# VestibularVR_H2-module_v1_1.net
KiCad netlist of a schematic drawn in EAGLE
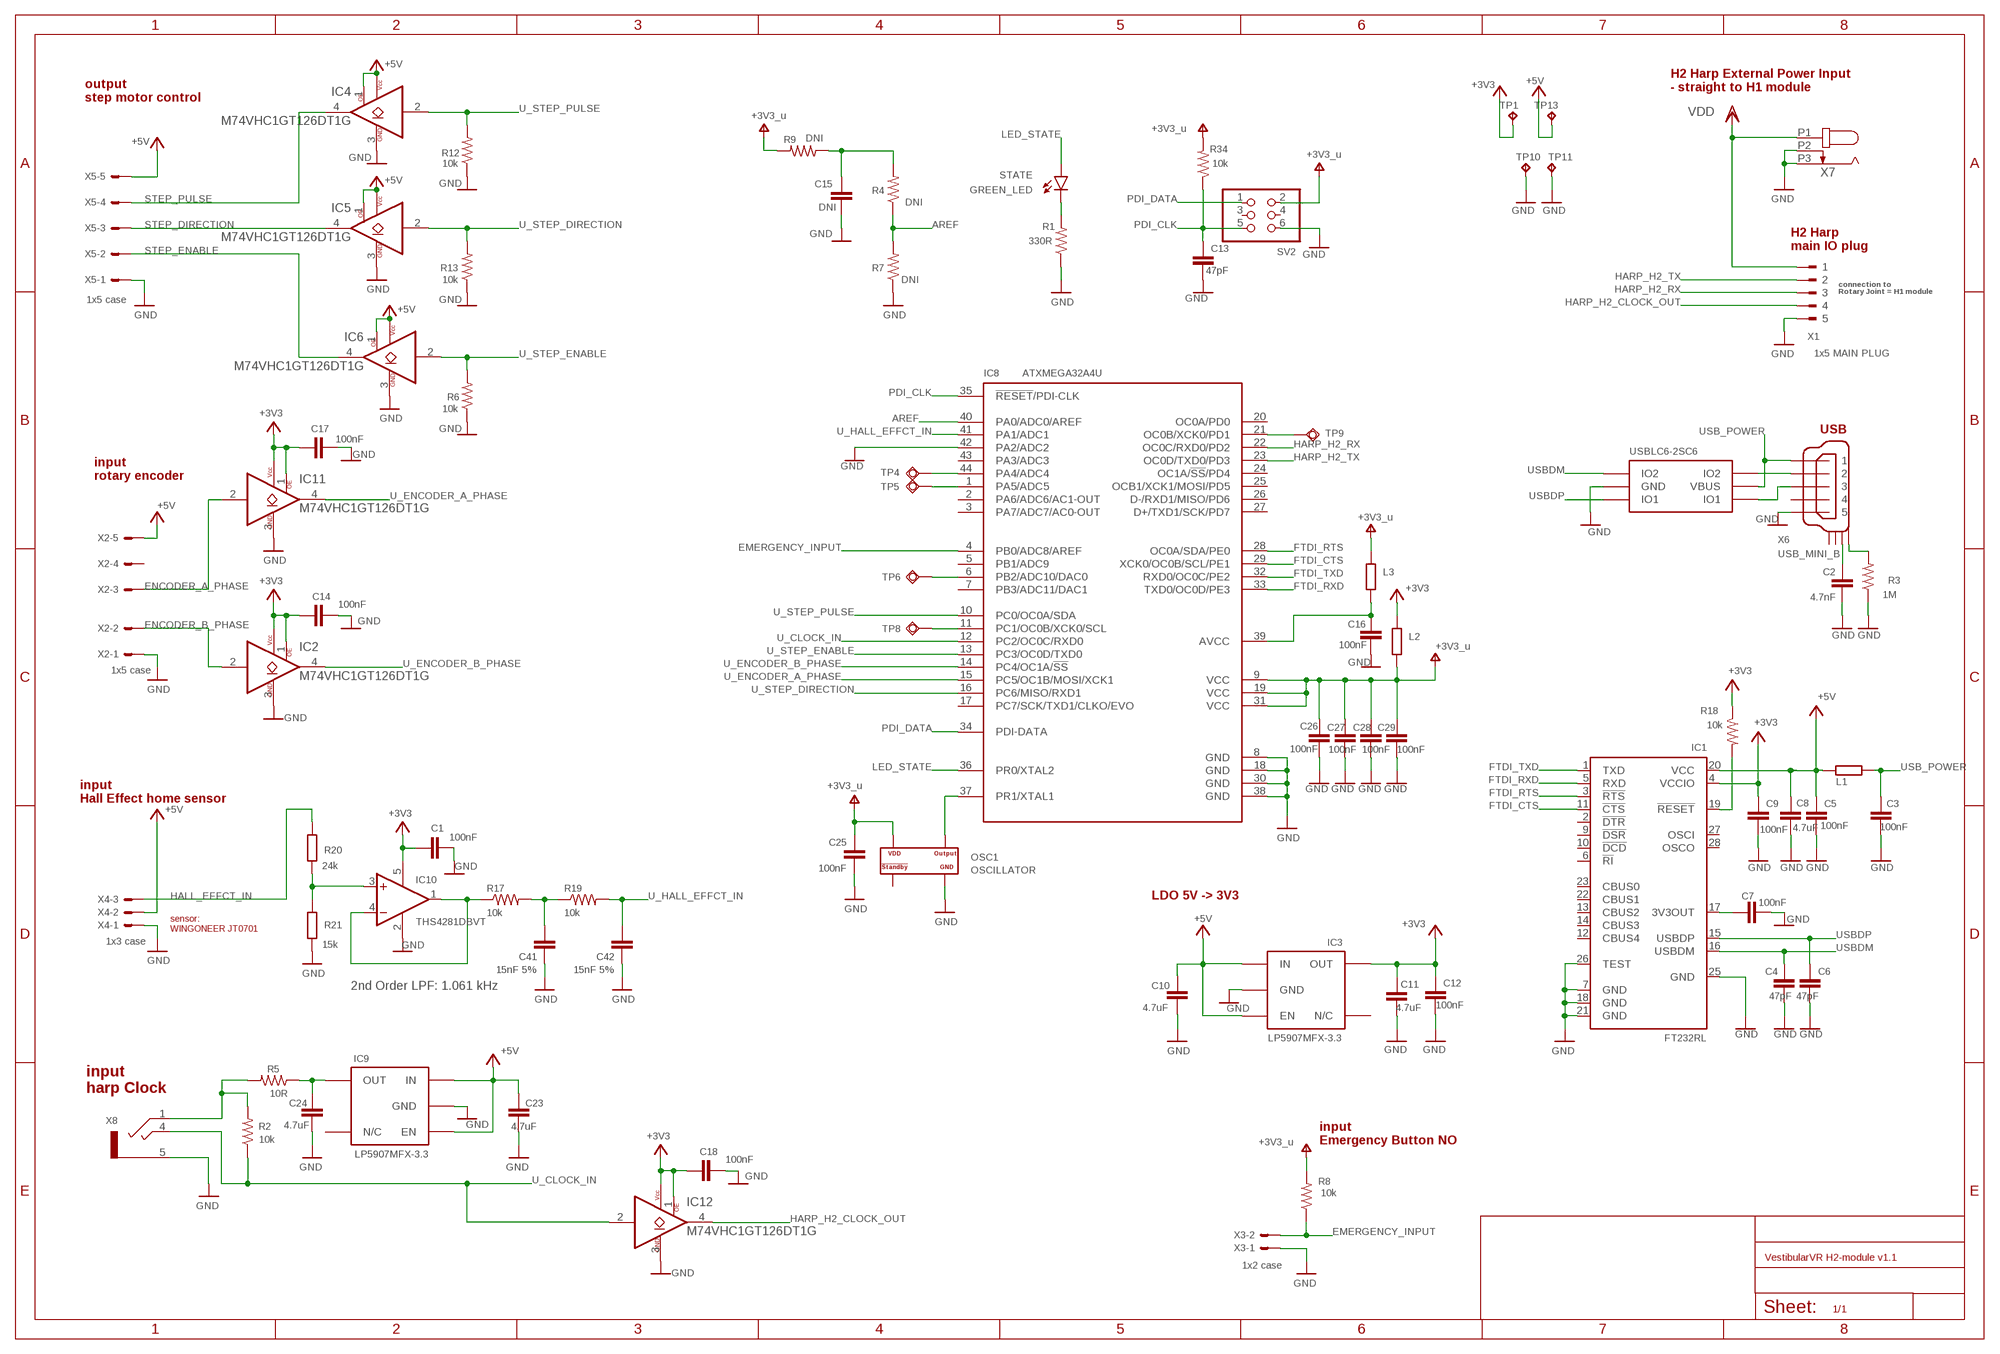
[diagram p0: schematic, sheet 1]

(export (version "E")
  (design (tool "Eeschema 10.0.6"))
  (components
    (comp (ref "C1")
      (value "100nF")
      (footprint "eagle-import:C0402K")
      (fields (field (name "MPN") "C1005X7R1H104K050BB"))
      (libsource (lib "eagle-import") (part "C-EUC0402K"))
    )
    (comp (ref "C2")
      (value "4.7nF")
      (footprint "eagle-import:C0402K")
      (fields (field (name "MPN") "CC0402KRX7R8BB472"))
      (libsource (lib "eagle-import") (part "C-EUC0402K"))
    )
    (comp (ref "C3")
      (value "100nF")
      (footprint "eagle-import:C0402K")
      (fields (field (name "MPN") "C1005X7R1H104K050BB"))
      (libsource (lib "eagle-import") (part "C-EUC0402K"))
    )
    (comp (ref "C4")
      (value "47pF")
      (footprint "eagle-import:C0402K")
      (fields (field (name "MPN") "04025A470JAT2A"))
      (libsource (lib "eagle-import") (part "C-EUC0402K"))
    )
    (comp (ref "C5")
      (value "100nF")
      (footprint "eagle-import:C0402K")
      (fields (field (name "MPN") "C1005X7R1H104K050BB"))
      (libsource (lib "eagle-import") (part "C-EUC0402K"))
    )
    (comp (ref "C6")
      (value "47pF")
      (footprint "eagle-import:C0402K")
      (fields (field (name "MPN") "04025A470JAT2A"))
      (libsource (lib "eagle-import") (part "C-EUC0402K"))
    )
    (comp (ref "C7")
      (value "100nF")
      (footprint "eagle-import:C0402K")
      (fields (field (name "MPN") "C1005X7R1H104K050BB"))
      (libsource (lib "eagle-import") (part "C-EUC0402K"))
    )
    (comp (ref "C8")
      (value "4.7uF")
      (footprint "eagle-import:C0603K")
      (fields (field (name "MPN") "C1608X6S1C475K080AC"))
      (libsource (lib "eagle-import") (part "C-EUC0603K"))
    )
    (comp (ref "C9")
      (value "100nF")
      (footprint "eagle-import:C0402K")
      (fields (field (name "MPN") "C1005X7R1H104K050BB"))
      (libsource (lib "eagle-import") (part "C-EUC0402K"))
    )
    (comp (ref "C10")
      (value "4.7uF")
      (footprint "eagle-import:C0603K")
      (fields (field (name "MPN") "C1608X6S1C475K080AC"))
      (libsource (lib "eagle-import") (part "C-EUC0603K"))
    )
    (comp (ref "C11")
      (value "4.7uF")
      (footprint "eagle-import:C0603K")
      (fields (field (name "MPN") "C1608X6S1C475K080AC"))
      (libsource (lib "eagle-import") (part "C-EUC0603K"))
    )
    (comp (ref "C12")
      (value "100nF")
      (footprint "eagle-import:C0402K")
      (fields (field (name "MPN") "C1005X7R1H104K050BB"))
      (libsource (lib "eagle-import") (part "C-EUC0402K"))
    )
    (comp (ref "C13")
      (value "47pF")
      (footprint "eagle-import:C0402K")
      (fields (field (name "MPN") "04025A470JAT2A"))
      (libsource (lib "eagle-import") (part "C-EUC0402K"))
    )
    (comp (ref "C14")
      (value "100nF")
      (footprint "eagle-import:C0402K")
      (fields (field (name "MPN") "C1005X7R1H104K050BB"))
      (libsource (lib "eagle-import") (part "C-EUC0402K"))
    )
    (comp (ref "C15")
      (value "DNI")
      (footprint "eagle-import:C0603K")
      (libsource (lib "eagle-import") (part "C-EUC0603K"))
    )
    (comp (ref "C16")
      (value "100nF")
      (footprint "eagle-import:C0402K")
      (fields (field (name "MPN") "C1005X7R1H104K050BB"))
      (libsource (lib "eagle-import") (part "C-EUC0402K"))
    )
    (comp (ref "C17")
      (value "100nF")
      (footprint "eagle-import:C0402K")
      (fields (field (name "MPN") "C1005X7R1H104K050BB"))
      (libsource (lib "eagle-import") (part "C-EUC0402K"))
    )
    (comp (ref "C18")
      (value "100nF")
      (footprint "eagle-import:C0402K")
      (fields (field (name "MPN") "C1005X7R1H104K050BB"))
      (libsource (lib "eagle-import") (part "C-EUC0402K"))
    )
    (comp (ref "C23")
      (value "4.7uF")
      (footprint "eagle-import:C0603K")
      (fields (field (name "MPN") "C1608X6S1C475K080AC"))
      (libsource (lib "eagle-import") (part "C-EUC0603K"))
    )
    (comp (ref "C24")
      (value "4.7uF")
      (footprint "eagle-import:C0603K")
      (fields (field (name "MPN") "C1608X6S1C475K080AC"))
      (libsource (lib "eagle-import") (part "C-EUC0603K"))
    )
    (comp (ref "C25")
      (value "100nF")
      (footprint "eagle-import:C0402K")
      (fields (field (name "MPN") "C1005X7R1H104K050BB"))
      (libsource (lib "eagle-import") (part "C-EUC0402K"))
    )
    (comp (ref "C26")
      (value "100nF")
      (footprint "eagle-import:C0402K")
      (fields (field (name "MPN") "C1005X7R1H104K050BB"))
      (libsource (lib "eagle-import") (part "C-EUC0402K"))
    )
    (comp (ref "C27")
      (value "100nF")
      (footprint "eagle-import:C0402K")
      (fields (field (name "MPN") "C1005X7R1H104K050BB"))
      (libsource (lib "eagle-import") (part "C-EUC0402K"))
    )
    (comp (ref "C28")
      (value "100nF")
      (footprint "eagle-import:C0402K")
      (fields (field (name "MPN") "C1005X7R1H104K050BB"))
      (libsource (lib "eagle-import") (part "C-EUC0402K"))
    )
    (comp (ref "C29")
      (value "100nF")
      (footprint "eagle-import:C0402K")
      (fields (field (name "MPN") "C1005X7R1H104K050BB"))
      (libsource (lib "eagle-import") (part "C-EUC0402K"))
    )
    (comp (ref "C41")
      (value "15nF 5%")
      (footprint "eagle-import:C0402K")
      (fields (field (name "MPN") "CGA2B3X7R1V153K050BB"))
      (libsource (lib "eagle-import") (part "C-EUC0402K"))
    )
    (comp (ref "C42")
      (value "15nF 5%")
      (footprint "eagle-import:C0402K")
      (fields (field (name "MPN") "CGA2B3X7R1V153K050BB"))
      (libsource (lib "eagle-import") (part "C-EUC0402K"))
    )
    (comp (ref "IC1")
      (value "FT232RL")
      (footprint "eagle-import:SSOP28")
      (libsource (lib "eagle-import") (part "FT232RL"))
    )
    (comp (ref "IC2")
      (value "M74VHC1GT126DT1G")
      (footprint "eagle-import:TSOP-5")
      (libsource (lib "eagle-import") (part "M74VHC1GT126DT1G"))
    )
    (comp (ref "IC3")
      (value "LP5907MFX-3.3")
      (footprint "eagle-import:TSOT23-5")
      (fields (field (name "MPN") "LP5907MFX-3.3/NOPB"))
      (libsource (lib "eagle-import") (part "TLV700XX"))
    )
    (comp (ref "IC4")
      (value "M74VHC1GT126DT1G")
      (footprint "eagle-import:TSOP-5")
      (libsource (lib "eagle-import") (part "M74VHC1GT126DT1G"))
    )
    (comp (ref "IC5")
      (value "M74VHC1GT126DT1G")
      (footprint "eagle-import:TSOP-5")
      (libsource (lib "eagle-import") (part "M74VHC1GT126DT1G"))
    )
    (comp (ref "IC6")
      (value "M74VHC1GT126DT1G")
      (footprint "eagle-import:TSOP-5")
      (libsource (lib "eagle-import") (part "M74VHC1GT126DT1G"))
    )
    (comp (ref "IC7")
      (value "USBLC6-2SC6")
      (footprint "eagle-import:SOT23-6L")
      (libsource (lib "eagle-import") (part "USBLC6-2SC6"))
    )
    (comp (ref "IC8")
      (value "ATXMEGA32A4U")
      (footprint "eagle-import:TQFP44")
      (fields (field (name "MPN") "ATXMEGA32A4U-AUR"))
      (libsource (lib "eagle-import") (part "XMEGA-A4_AT-XMEGA-XXA4-AUTQFP44"))
    )
    (comp (ref "IC9")
      (value "LP5907MFX-3.3")
      (footprint "eagle-import:TSOT23-5")
      (fields (field (name "MPN") "LP5907MFX-3.3/NOPB"))
      (libsource (lib "eagle-import") (part "TLV700XX"))
    )
    (comp (ref "IC10")
      (value "THS4281DBVT")
      (footprint "eagle-import:SOT23-5")
      (libsource (lib "eagle-import") (part "OPA365"))
    )
    (comp (ref "IC11")
      (value "M74VHC1GT126DT1G")
      (footprint "eagle-import:TSOP-5")
      (libsource (lib "eagle-import") (part "M74VHC1GT126DT1G"))
    )
    (comp (ref "IC12")
      (value "M74VHC1GT126DT1G")
      (footprint "eagle-import:TSOP-5")
      (libsource (lib "eagle-import") (part "M74VHC1GT126DT1G"))
    )
    (comp (ref "L1")
      (value "40R@100MHz")
      (footprint "eagle-import:R0805")
      (fields (field (name "MPN") "MI0805K400R-10"))
      (libsource (lib "eagle-import") (part "R-EU_R0805"))
    )
    (comp (ref "L2")
      (value "40R@100MHz")
      (footprint "eagle-import:R0805")
      (fields (field (name "MPN") "MI0805K400R-10"))
      (libsource (lib "eagle-import") (part "R-EU_R0805"))
    )
    (comp (ref "L3")
      (value "40R@100MHz")
      (footprint "eagle-import:R0805")
      (fields (field (name "MPN") "MI0805K400R-10"))
      (libsource (lib "eagle-import") (part "R-EU_R0805"))
    )
    (comp (ref "OSC1")
      (value "OSCILLATOR")
      (footprint "eagle-import:OSCILLATOR_3.2X2.5")
      (fields (field (name "MPN") "DSC1001CI5-032.0000"))
      (libsource (lib "eagle-import") (part "OSCILLATOR"))
    )
    (comp (ref "R1")
      (value "330R")
      (footprint "eagle-import:R0402")
      (fields (field (name "MPN") "RC0402FR-07330RL"))
      (libsource (lib "eagle-import") (part "R-US_R0402"))
    )
    (comp (ref "R2")
      (value "10k")
      (footprint "eagle-import:R0402")
      (fields (field (name "MPN") "CRCW040210K0FKED"))
      (libsource (lib "eagle-import") (part "R-US_R0402"))
    )
    (comp (ref "R3")
      (value "1M")
      (footprint "eagle-import:R0402")
      (fields (field (name "MPN") "CRCW04021M00FKED"))
      (libsource (lib "eagle-import") (part "R-US_R0402"))
    )
    (comp (ref "R4")
      (value "DNI")
      (footprint "eagle-import:R0402")
      (libsource (lib "eagle-import") (part "R-US_R0402"))
    )
    (comp (ref "R5")
      (value "10R")
      (footprint "eagle-import:R0402")
      (fields (field (name "MPN") "ERJ-PA2J100X "))
      (libsource (lib "eagle-import") (part "R-US_R0402"))
    )
    (comp (ref "R6")
      (value "10k")
      (footprint "eagle-import:R0402")
      (fields (field (name "MPN") "CRCW040210K0FKED"))
      (libsource (lib "eagle-import") (part "R-US_R0402"))
    )
    (comp (ref "R7")
      (value "DNI")
      (footprint "eagle-import:R0402")
      (libsource (lib "eagle-import") (part "R-US_R0402"))
    )
    (comp (ref "R8")
      (value "10k")
      (footprint "eagle-import:R0402")
      (fields (field (name "MPN") "CRCW040210K0FKED"))
      (libsource (lib "eagle-import") (part "R-US_R0402"))
    )
    (comp (ref "R9")
      (value "DNI")
      (footprint "eagle-import:R0402")
      (libsource (lib "eagle-import") (part "R-US_R0402"))
    )
    (comp (ref "R12")
      (value "10k")
      (footprint "eagle-import:R0402")
      (fields (field (name "MPN") "CRCW040210K0FKED"))
      (libsource (lib "eagle-import") (part "R-US_R0402"))
    )
    (comp (ref "R13")
      (value "10k")
      (footprint "eagle-import:R0402")
      (fields (field (name "MPN") "CRCW040210K0FKED"))
      (libsource (lib "eagle-import") (part "R-US_R0402"))
    )
    (comp (ref "R17")
      (value "10k")
      (footprint "eagle-import:R0402")
      (fields (field (name "MPN") "CRCW040210K0FKED"))
      (libsource (lib "eagle-import") (part "R-US_R0402"))
    )
    (comp (ref "R18")
      (value "10k")
      (footprint "eagle-import:R0402")
      (fields (field (name "MPN") "CRCW040210K0FKED"))
      (libsource (lib "eagle-import") (part "R-US_R0402"))
    )
    (comp (ref "R19")
      (value "10k")
      (footprint "eagle-import:R0402")
      (fields (field (name "MPN") "CRCW040210K0FKED"))
      (libsource (lib "eagle-import") (part "R-US_R0402"))
    )
    (comp (ref "R20")
      (value "24k")
      (footprint "eagle-import:R0402")
      (fields (field (name "MPN") "ERJ-2RKF2402X"))
      (libsource (lib "eagle-import") (part "R-EU_R0402"))
    )
    (comp (ref "R21")
      (value "15k")
      (footprint "eagle-import:R0402")
      (fields (field (name "MPN") "ERJ-2RKF1502X"))
      (libsource (lib "eagle-import") (part "R-EU_R0402"))
    )
    (comp (ref "R34")
      (value "10k")
      (footprint "eagle-import:R0402")
      (fields (field (name "MPN") "CRCW040210K0FKED"))
      (libsource (lib "eagle-import") (part "R-US_R0402"))
    )
    (comp (ref "STATE")
      (value "GREEN_LED")
      (footprint "eagle-import:CHIP-LED0603")
      (fields (field (name "MPN") "LTST-C191KGKT"))
      (libsource (lib "eagle-import") (part "LEDCHIP-LED0603"))
    )
    (comp (ref "SV2")
      (value "PINHD-2X3")
      (footprint "eagle-import:2X03")
      (fields (field (name "MPN") "609-3210-ND"))
      (libsource (lib "eagle-import") (part "PINHD-2X3"))
    )
    (comp (ref "TP1")
      (value "NO_COMPONENT")
      (footprint "eagle-import:B1,27")
      (libsource (lib "eagle-import") (part "TPB1,27"))
    )
    (comp (ref "TP4")
      (value "NO_COMPONENT")
      (footprint "eagle-import:TP11R")
      (libsource (lib "eagle-import") (part "TPSQTP11R"))
    )
    (comp (ref "TP5")
      (value "NO_COMPONENT")
      (footprint "eagle-import:TP11R")
      (libsource (lib "eagle-import") (part "TPSQTP11R"))
    )
    (comp (ref "TP6")
      (value "NO_COMPONENT")
      (footprint "eagle-import:TP11R")
      (libsource (lib "eagle-import") (part "TPSQTP11R"))
    )
    (comp (ref "TP8")
      (value "NO_COMPONENT")
      (footprint "eagle-import:TP11R")
      (libsource (lib "eagle-import") (part "TPSQTP11R"))
    )
    (comp (ref "TP9")
      (value "NO_COMPONENT")
      (footprint "eagle-import:TP11R")
      (libsource (lib "eagle-import") (part "TPSQTP11R"))
    )
    (comp (ref "TP10")
      (value "NO_COMPONENT")
      (footprint "eagle-import:B1,27")
      (libsource (lib "eagle-import") (part "TPB1,27"))
    )
    (comp (ref "TP11")
      (value "NO_COMPONENT")
      (footprint "eagle-import:B1,27")
      (libsource (lib "eagle-import") (part "TPB1,27"))
    )
    (comp (ref "TP13")
      (value "NO_COMPONENT")
      (footprint "eagle-import:B1,27")
      (libsource (lib "eagle-import") (part "TPB1,27"))
    )
    (comp (ref "X1")
      (value "1x5 MAIN PLUG")
      (footprint "eagle-import:90G-5")
      (fields (field (name "MPN") "20.155MH/5-E"))
      (libsource (lib "eagle-import") (part "90G-5"))
    )
    (comp (ref "X2")
      (value "1x5 case")
      (footprint "eagle-import:22-23-2051")
      (fields (field (name "MPN") "282834-5") (field (name "OEPS") "OEPS070041"))
      (libsource (lib "eagle-import") (part "22-23-2051"))
    )
    (comp (ref "X3")
      (value "1x2 case")
      (footprint "eagle-import:22-23-2021")
      (fields (field (name "MPN") "282834-2"))
      (libsource (lib "eagle-import") (part "22-23-2021"))
    )
    (comp (ref "X4")
      (value "1x3 case")
      (footprint "eagle-import:22-23-2031")
      (fields (field (name "MPN") "282834-3") (field (name "OEPS") "OEPS070035"))
      (libsource (lib "eagle-import") (part "22-23-2031"))
    )
    (comp (ref "X5")
      (value "1x5 case")
      (footprint "eagle-import:22-23-2051")
      (fields (field (name "MPN") "282834-5") (field (name "OEPS") "OEPS070041"))
      (libsource (lib "eagle-import") (part "22-23-2051"))
    )
    (comp (ref "X6")
      (value "USB_MINI_B")
      (footprint "eagle-import:240-0002-1")
      (fields (field (name "MPN") "UX60-MB-5S8"))
      (libsource (lib "eagle-import") (part "USB_MINI_B"))
    )
    (comp (ref "X7")
      (value "DC_JACK2.1MM")
      (footprint "eagle-import:DC_POWER_INPUT_2.1MM")
      (fields (field (name "MPN") "163-179PH-EX"))
      (libsource (lib "eagle-import") (part "DC_JACK2.1MM"))
    )
    (comp (ref "X8")
      (value "CLCK_JACK")
      (footprint "eagle-import:35RASMT2BHNTRX")
      (fields (field (name "MPN") "35RASMT2BHNTRX"))
      (libsource (lib "eagle-import") (part "STEREO_JACK"))
    )
  )
  (nets
    (net (code "1") (name "+3V3") (class "Default")
      (node (ref "C1") (pin "1") (pinfunction "1_1") (pintype "passive"))
      (node (ref "C11") (pin "1") (pinfunction "1_1") (pintype "passive"))
      (node (ref "C12") (pin "1") (pinfunction "1_1") (pintype "passive"))
      (node (ref "C14") (pin "1") (pinfunction "1_1") (pintype "passive"))
      (node (ref "C17") (pin "1") (pinfunction "1_1") (pintype "passive"))
      (node (ref "C18") (pin "1") (pinfunction "1_1") (pintype "passive"))
      (node (ref "C9") (pin "1") (pinfunction "1_1") (pintype "passive"))
      (node (ref "IC1") (pin "4") (pinfunction "VCCIO_4") (pintype "power_in"))
      (node (ref "IC10") (pin "5") (pinfunction "V+_5") (pintype "power_in"))
      (node (ref "IC11") (pin "1") (pinfunction "OE_1") (pintype "bidirectional"))
      (node (ref "IC11") (pin "5") (pinfunction "VCC_5") (pintype "bidirectional"))
      (node (ref "IC12") (pin "1") (pinfunction "OE_1") (pintype "bidirectional"))
      (node (ref "IC12") (pin "5") (pinfunction "VCC_5") (pintype "bidirectional"))
      (node (ref "IC2") (pin "1") (pinfunction "OE_1") (pintype "bidirectional"))
      (node (ref "IC2") (pin "5") (pinfunction "VCC_5") (pintype "bidirectional"))
      (node (ref "IC3") (pin "5") (pinfunction "OUT_5") (pintype "bidirectional"))
      (node (ref "L2") (pin "2") (pinfunction "2_2") (pintype "passive"))
      (node (ref "R18") (pin "1") (pinfunction "1_1") (pintype "passive"))
      (node (ref "TP1") (pin "TP") (pinfunction "TP_TP") (pintype "input"))
    )
    (net (code "2") (name "+3V3_u") (class "Default")
      (node (ref "C25") (pin "1") (pinfunction "1_1") (pintype "passive"))
      (node (ref "C26") (pin "1") (pinfunction "1_1") (pintype "passive"))
      (node (ref "C27") (pin "1") (pinfunction "1_1") (pintype "passive"))
      (node (ref "C28") (pin "1") (pinfunction "1_1") (pintype "passive"))
      (node (ref "C29") (pin "1") (pinfunction "1_1") (pintype "passive"))
      (node (ref "IC8") (pin "19") (pinfunction "VCC_19") (pintype "power_in"))
      (node (ref "IC8") (pin "31") (pinfunction "VCC_31") (pintype "power_in"))
      (node (ref "IC8") (pin "9") (pinfunction "VCC_9") (pintype "power_in"))
      (node (ref "L2") (pin "1") (pinfunction "1_1") (pintype "passive"))
      (node (ref "L3") (pin "2") (pinfunction "2_2") (pintype "passive"))
      (node (ref "OSC1") (pin "P$4") (pinfunction "VDD_P$4") (pintype "passive"))
      (node (ref "R34") (pin "2") (pinfunction "2_2") (pintype "passive"))
      (node (ref "R8") (pin "2") (pinfunction "2_2") (pintype "passive"))
      (node (ref "R9") (pin "2") (pinfunction "2_2") (pintype "passive"))
      (node (ref "SV2") (pin "2") (pinfunction "2_2") (pintype "passive"))
    )
    (net (code "3") (name "+5V") (class "Default")
      (node (ref "C10") (pin "1") (pinfunction "1_1") (pintype "passive"))
      (node (ref "C23") (pin "1") (pinfunction "1_1") (pintype "passive"))
      (node (ref "C5") (pin "1") (pinfunction "1_1") (pintype "passive"))
      (node (ref "C8") (pin "1") (pinfunction "1_1") (pintype "passive"))
      (node (ref "IC1") (pin "20") (pinfunction "VCC_20") (pintype "power_in"))
      (node (ref "IC3") (pin "1") (pinfunction "IN_1") (pintype "bidirectional"))
      (node (ref "IC3") (pin "3") (pinfunction "EN_3") (pintype "bidirectional"))
      (node (ref "IC4") (pin "1") (pinfunction "OE_1") (pintype "bidirectional"))
      (node (ref "IC4") (pin "5") (pinfunction "VCC_5") (pintype "bidirectional"))
      (node (ref "IC5") (pin "1") (pinfunction "OE_1") (pintype "bidirectional"))
      (node (ref "IC5") (pin "5") (pinfunction "VCC_5") (pintype "bidirectional"))
      (node (ref "IC6") (pin "1") (pinfunction "OE_1") (pintype "bidirectional"))
      (node (ref "IC6") (pin "5") (pinfunction "VCC_5") (pintype "bidirectional"))
      (node (ref "IC9") (pin "1") (pinfunction "IN_1") (pintype "bidirectional"))
      (node (ref "IC9") (pin "3") (pinfunction "EN_3") (pintype "bidirectional"))
      (node (ref "L1") (pin "1") (pinfunction "1_1") (pintype "passive"))
      (node (ref "TP13") (pin "TP") (pinfunction "TP_TP") (pintype "input"))
      (node (ref "X2") (pin "5") (pinfunction "S_5") (pintype "passive"))
      (node (ref "X4") (pin "2") (pinfunction "S_2") (pintype "passive"))
      (node (ref "X5") (pin "5") (pinfunction "S_5") (pintype "passive"))
    )
    (net (code "4") (name "/AREF") (class "Default")
      (node (ref "IC8") (pin "40") (pinfunction "PA0/ADC0/AREF_40") (pintype "bidirectional"))
      (node (ref "R4") (pin "1") (pinfunction "1_1") (pintype "passive"))
      (node (ref "R7") (pin "2") (pinfunction "2_2") (pintype "passive"))
    )
    (net (code "5") (name "/EMERGENCY_INPUT") (class "Default")
      (node (ref "IC8") (pin "4") (pinfunction "PB0/ADC8/AREF_4") (pintype "bidirectional"))
      (node (ref "R8") (pin "1") (pinfunction "1_1") (pintype "passive"))
      (node (ref "X3") (pin "2") (pinfunction "S_2") (pintype "passive"))
    )
    (net (code "6") (name "/ENCODER_A_PHASE") (class "Default")
      (node (ref "IC11") (pin "2") (pinfunction "A_2") (pintype "bidirectional"))
      (node (ref "X2") (pin "3") (pinfunction "S_3") (pintype "passive"))
    )
    (net (code "7") (name "/ENCODER_B_PHASE") (class "Default")
      (node (ref "IC2") (pin "2") (pinfunction "A_2") (pintype "bidirectional"))
      (node (ref "X2") (pin "2") (pinfunction "S_2") (pintype "passive"))
    )
    (net (code "8") (name "/FTDI_CTS") (class "Default")
      (node (ref "IC1") (pin "11") (pinfunction "~{CTS}_11") (pintype "input"))
      (node (ref "IC8") (pin "29") (pinfunction "XCK0/OC0B/SCL/PE1_29") (pintype "bidirectional"))
    )
    (net (code "9") (name "/FTDI_RTS") (class "Default")
      (node (ref "IC1") (pin "3") (pinfunction "~{RTS}_3") (pintype "output"))
      (node (ref "IC8") (pin "28") (pinfunction "OC0A/SDA/PE0_28") (pintype "bidirectional"))
    )
    (net (code "10") (name "/FTDI_RXD") (class "Default")
      (node (ref "IC1") (pin "5") (pinfunction "RXD_5") (pintype "input"))
      (node (ref "IC8") (pin "33") (pinfunction "TXD0/OC0D/PE3_33") (pintype "bidirectional"))
    )
    (net (code "11") (name "/FTDI_TXD") (class "Default")
      (node (ref "IC1") (pin "1") (pinfunction "TXD_1") (pintype "output"))
      (node (ref "IC8") (pin "32") (pinfunction "RXD0/OC0C/PE2_32") (pintype "bidirectional"))
    )
    (net (code "12") (name "/HALL_EFFCT_IN") (class "Default")
      (node (ref "R20") (pin "2") (pinfunction "2_2") (pintype "passive"))
      (node (ref "X4") (pin "3") (pinfunction "S_3") (pintype "passive"))
    )
    (net (code "13") (name "/HARP_H2_CLOCK_OUT") (class "Default")
      (node (ref "IC12") (pin "4") (pinfunction "Y_4") (pintype "bidirectional"))
      (node (ref "X1") (pin "4") (pinfunction "4_4") (pintype "passive"))
    )
    (net (code "14") (name "/HARP_H2_RX") (class "Default")
      (node (ref "IC8") (pin "22") (pinfunction "OC0C/RXD0/PD2_22") (pintype "bidirectional"))
      (node (ref "X1") (pin "3") (pinfunction "3_3") (pintype "passive"))
    )
    (net (code "15") (name "/HARP_H2_TX") (class "Default")
      (node (ref "IC8") (pin "23") (pinfunction "OC0D/TXD0/PD3_23") (pintype "bidirectional"))
      (node (ref "X1") (pin "2") (pinfunction "2_2") (pintype "passive"))
    )
    (net (code "16") (name "/LED_STATE") (class "Default")
      (node (ref "IC8") (pin "36") (pinfunction "PR0/XTAL2_36") (pintype "bidirectional"))
      (node (ref "STATE") (pin "A") (pinfunction "A_A") (pintype "passive"))
    )
    (net (code "17") (name "/PDI_CLK") (class "Default")
      (node (ref "C13") (pin "1") (pinfunction "1_1") (pintype "passive"))
      (node (ref "IC8") (pin "35") (pinfunction "~{RESET}/PDI-CLK_35") (pintype "input"))
      (node (ref "R34") (pin "1") (pinfunction "1_1") (pintype "passive"))
      (node (ref "SV2") (pin "5") (pinfunction "5_5") (pintype "passive"))
    )
    (net (code "18") (name "/PDI_DATA") (class "Default")
      (node (ref "IC8") (pin "34") (pinfunction "PDI-DATA_34") (pintype "bidirectional"))
      (node (ref "SV2") (pin "1") (pinfunction "1_1") (pintype "passive"))
    )
    (net (code "19") (name "/STEP_DIRECTION") (class "Default")
      (node (ref "IC5") (pin "4") (pinfunction "Y_4") (pintype "bidirectional"))
      (node (ref "X5") (pin "3") (pinfunction "S_3") (pintype "passive"))
    )
    (net (code "20") (name "/STEP_ENABLE") (class "Default")
      (node (ref "IC6") (pin "4") (pinfunction "Y_4") (pintype "bidirectional"))
      (node (ref "X5") (pin "2") (pinfunction "S_2") (pintype "passive"))
    )
    (net (code "21") (name "/STEP_PULSE") (class "Default")
      (node (ref "IC4") (pin "4") (pinfunction "Y_4") (pintype "bidirectional"))
      (node (ref "X5") (pin "4") (pinfunction "S_4") (pintype "passive"))
    )
    (net (code "22") (name "/USBDM") (class "Default")
      (node (ref "C4") (pin "1") (pinfunction "1_1") (pintype "passive"))
      (node (ref "IC1") (pin "16") (pinfunction "USBDM_16") (pintype "bidirectional"))
      (node (ref "IC7") (pin "P$3") (pinfunction "IO2_P$3") (pintype "bidirectional"))
    )
    (net (code "23") (name "/USBDP") (class "Default")
      (node (ref "C6") (pin "1") (pinfunction "1_1") (pintype "passive"))
      (node (ref "IC1") (pin "15") (pinfunction "USBDP_15") (pintype "bidirectional"))
      (node (ref "IC7") (pin "P$1") (pinfunction "IO1_P$1") (pintype "bidirectional"))
    )
    (net (code "24") (name "/USB_POWER") (class "Default")
      (node (ref "C3") (pin "1") (pinfunction "1_1") (pintype "passive"))
      (node (ref "IC7") (pin "P$5") (pinfunction "VBUS_P$5") (pintype "bidirectional"))
      (node (ref "L1") (pin "2") (pinfunction "2_2") (pintype "passive"))
      (node (ref "X6") (pin "P$1") (pinfunction "1_P$1") (pintype "bidirectional"))
    )
    (net (code "25") (name "/U_CLOCK_IN") (class "Default")
      (node (ref "IC12") (pin "2") (pinfunction "A_2") (pintype "bidirectional"))
      (node (ref "IC8") (pin "12") (pinfunction "PC2/OC0C/RXD0_12") (pintype "bidirectional"))
      (node (ref "R2") (pin "1") (pinfunction "1_1") (pintype "passive"))
      (node (ref "X8") (pin "4") (pinfunction "4_4") (pintype "passive"))
    )
    (net (code "26") (name "/U_ENCODER_A_PHASE") (class "Default")
      (node (ref "IC11") (pin "4") (pinfunction "Y_4") (pintype "bidirectional"))
      (node (ref "IC8") (pin "15") (pinfunction "PC5/OC1B/MOSI/XCK1_15") (pintype "bidirectional"))
    )
    (net (code "27") (name "/U_ENCODER_B_PHASE") (class "Default")
      (node (ref "IC2") (pin "4") (pinfunction "Y_4") (pintype "bidirectional"))
      (node (ref "IC8") (pin "14") (pinfunction "PC4/OC1A/~{SS}_14") (pintype "bidirectional"))
    )
    (net (code "28") (name "/U_HALL_EFFCT_IN") (class "Default")
      (node (ref "C42") (pin "2") (pinfunction "2_2") (pintype "passive"))
      (node (ref "IC8") (pin "41") (pinfunction "PA1/ADC1_41") (pintype "bidirectional"))
      (node (ref "R19") (pin "2") (pinfunction "2_2") (pintype "passive"))
    )
    (net (code "29") (name "/U_STEP_DIRECTION") (class "Default")
      (node (ref "IC5") (pin "2") (pinfunction "A_2") (pintype "bidirectional"))
      (node (ref "IC8") (pin "16") (pinfunction "PC6/MISO/RXD1_16") (pintype "bidirectional"))
      (node (ref "R13") (pin "2") (pinfunction "2_2") (pintype "passive"))
    )
    (net (code "30") (name "/U_STEP_ENABLE") (class "Default")
      (node (ref "IC6") (pin "2") (pinfunction "A_2") (pintype "bidirectional"))
      (node (ref "IC8") (pin "13") (pinfunction "PC3/OC0D/TXD0_13") (pintype "bidirectional"))
      (node (ref "R6") (pin "2") (pinfunction "2_2") (pintype "passive"))
    )
    (net (code "31") (name "/U_STEP_PULSE") (class "Default")
      (node (ref "IC4") (pin "2") (pinfunction "A_2") (pintype "bidirectional"))
      (node (ref "IC8") (pin "10") (pinfunction "PC0/OC0A/SDA_10") (pintype "bidirectional"))
      (node (ref "R12") (pin "2") (pinfunction "2_2") (pintype "passive"))
    )
    (net (code "32") (name "GND") (class "Default")
      (node (ref "C1") (pin "2") (pinfunction "2_2") (pintype "passive"))
      (node (ref "C10") (pin "2") (pinfunction "2_2") (pintype "passive"))
      (node (ref "C11") (pin "2") (pinfunction "2_2") (pintype "passive"))
      (node (ref "C12") (pin "2") (pinfunction "2_2") (pintype "passive"))
      (node (ref "C13") (pin "2") (pinfunction "2_2") (pintype "passive"))
      (node (ref "C14") (pin "2") (pinfunction "2_2") (pintype "passive"))
      (node (ref "C15") (pin "2") (pinfunction "2_2") (pintype "passive"))
      (node (ref "C16") (pin "2") (pinfunction "2_2") (pintype "passive"))
      (node (ref "C17") (pin "2") (pinfunction "2_2") (pintype "passive"))
      (node (ref "C18") (pin "2") (pinfunction "2_2") (pintype "passive"))
      (node (ref "C2") (pin "2") (pinfunction "2_2") (pintype "passive"))
      (node (ref "C23") (pin "2") (pinfunction "2_2") (pintype "passive"))
      (node (ref "C24") (pin "2") (pinfunction "2_2") (pintype "passive"))
      (node (ref "C25") (pin "2") (pinfunction "2_2") (pintype "passive"))
      (node (ref "C26") (pin "2") (pinfunction "2_2") (pintype "passive"))
      (node (ref "C27") (pin "2") (pinfunction "2_2") (pintype "passive"))
      (node (ref "C28") (pin "2") (pinfunction "2_2") (pintype "passive"))
      (node (ref "C29") (pin "2") (pinfunction "2_2") (pintype "passive"))
      (node (ref "C3") (pin "2") (pinfunction "2_2") (pintype "passive"))
      (node (ref "C4") (pin "2") (pinfunction "2_2") (pintype "passive"))
      (node (ref "C41") (pin "1") (pinfunction "1_1") (pintype "passive"))
      (node (ref "C42") (pin "1") (pinfunction "1_1") (pintype "passive"))
      (node (ref "C5") (pin "2") (pinfunction "2_2") (pintype "passive"))
      (node (ref "C6") (pin "2") (pinfunction "2_2") (pintype "passive"))
      (node (ref "C7") (pin "2") (pinfunction "2_2") (pintype "passive"))
      (node (ref "C8") (pin "2") (pinfunction "2_2") (pintype "passive"))
      (node (ref "C9") (pin "2") (pinfunction "2_2") (pintype "passive"))
      (node (ref "IC1") (pin "18") (pinfunction "GND_18") (pintype "power_in"))
      (node (ref "IC1") (pin "21") (pinfunction "GND_21") (pintype "power_in"))
      (node (ref "IC1") (pin "25") (pinfunction "GND_25") (pintype "power_in"))
      (node (ref "IC1") (pin "26") (pinfunction "TEST_26") (pintype "input"))
      (node (ref "IC1") (pin "7") (pinfunction "GND_7") (pintype "power_in"))
      (node (ref "IC10") (pin "2") (pinfunction "V-_2") (pintype "power_in"))
      (node (ref "IC11") (pin "3") (pinfunction "GND_3") (pintype "bidirectional"))
      (node (ref "IC12") (pin "3") (pinfunction "GND_3") (pintype "bidirectional"))
      (node (ref "IC2") (pin "3") (pinfunction "GND_3") (pintype "bidirectional"))
      (node (ref "IC3") (pin "2") (pinfunction "GND_2") (pintype "bidirectional"))
      (node (ref "IC4") (pin "3") (pinfunction "GND_3") (pintype "bidirectional"))
      (node (ref "IC5") (pin "3") (pinfunction "GND_3") (pintype "bidirectional"))
      (node (ref "IC6") (pin "3") (pinfunction "GND_3") (pintype "bidirectional"))
      (node (ref "IC7") (pin "P$2") (pinfunction "GND_P$2") (pintype "bidirectional"))
      (node (ref "IC8") (pin "18") (pinfunction "GND_18") (pintype "power_in"))
      (node (ref "IC8") (pin "30") (pinfunction "GND_30") (pintype "power_in"))
      (node (ref "IC8") (pin "38") (pinfunction "GND_38") (pintype "power_in"))
      (node (ref "IC8") (pin "42") (pinfunction "PA2/ADC2_42") (pintype "bidirectional"))
      (node (ref "IC8") (pin "8") (pinfunction "GND_8") (pintype "power_in"))
      (node (ref "IC9") (pin "2") (pinfunction "GND_2") (pintype "bidirectional"))
      (node (ref "OSC1") (pin "P$2") (pinfunction "GND_P$2") (pintype "passive"))
      (node (ref "R1") (pin "1") (pinfunction "1_1") (pintype "passive"))
      (node (ref "R12") (pin "1") (pinfunction "1_1") (pintype "passive"))
      (node (ref "R13") (pin "1") (pinfunction "1_1") (pintype "passive"))
      (node (ref "R21") (pin "1") (pinfunction "1_1") (pintype "passive"))
      (node (ref "R3") (pin "1") (pinfunction "1_1") (pintype "passive"))
      (node (ref "R6") (pin "1") (pinfunction "1_1") (pintype "passive"))
      (node (ref "R7") (pin "1") (pinfunction "1_1") (pintype "passive"))
      (node (ref "SV2") (pin "6") (pinfunction "6_6") (pintype "passive"))
      (node (ref "TP10") (pin "TP") (pinfunction "TP_TP") (pintype "input"))
      (node (ref "TP11") (pin "TP") (pinfunction "TP_TP") (pintype "input"))
      (node (ref "X1") (pin "5") (pinfunction "5_5") (pintype "passive"))
      (node (ref "X2") (pin "1") (pinfunction "S_1") (pintype "passive"))
      (node (ref "X3") (pin "1") (pinfunction "S_1") (pintype "passive"))
      (node (ref "X4") (pin "1") (pinfunction "S_1") (pintype "passive"))
      (node (ref "X5") (pin "1") (pinfunction "S_1") (pintype "passive"))
      (node (ref "X6") (pin "P$5") (pinfunction "5_P$5") (pintype "bidirectional"))
      (node (ref "X7") (pin "P2") (pinfunction "2_P2") (pintype "passive"))
      (node (ref "X7") (pin "P3") (pinfunction "3_P3") (pintype "passive"))
      (node (ref "X8") (pin "5") (pinfunction "5_5") (pintype "passive"))
    )
    (net (code "33") (name "Net-(C15-Pad1)") (class "Default")
      (node (ref "C15") (pin "1") (pinfunction "1_1") (pintype "passive"))
      (node (ref "R4") (pin "2") (pinfunction "2_2") (pintype "passive"))
      (node (ref "R9") (pin "1") (pinfunction "1_1") (pintype "passive"))
    )
    (net (code "34") (name "Net-(C41-Pad2)") (class "Default")
      (node (ref "C41") (pin "2") (pinfunction "2_2") (pintype "passive"))
      (node (ref "R17") (pin "2") (pinfunction "2_2") (pintype "passive"))
      (node (ref "R19") (pin "1") (pinfunction "1_1") (pintype "passive"))
    )
    (net (code "35") (name "Net-(IC1-3V3OUT)") (class "Default")
      (node (ref "C7") (pin "1") (pinfunction "1_1") (pintype "passive"))
      (node (ref "IC1") (pin "17") (pinfunction "3V3OUT_17") (pintype "output"))
    )
    (net (code "36") (name "Net-(IC1-~{RESET})") (class "Default")
      (node (ref "IC1") (pin "19") (pinfunction "~{RESET}_19") (pintype "input"))
      (node (ref "R18") (pin "2") (pinfunction "2_2") (pintype "passive"))
    )
    (net (code "37") (name "Net-(IC8-AVCC)") (class "Default")
      (node (ref "C16") (pin "1") (pinfunction "1_1") (pintype "passive"))
      (node (ref "IC8") (pin "39") (pinfunction "AVCC_39") (pintype "power_in"))
      (node (ref "L3") (pin "1") (pinfunction "1_1") (pintype "passive"))
    )
    (net (code "38") (name "Net-(IC8-OC0B{slash}XCK0{slash}PD1)") (class "Default")
      (node (ref "IC8") (pin "21") (pinfunction "OC0B/XCK0/PD1_21") (pintype "bidirectional"))
      (node (ref "TP9") (pin "TP") (pinfunction "TP_TP") (pintype "input"))
    )
    (net (code "39") (name "Net-(IC8-PA4{slash}ADC4)") (class "Default")
      (node (ref "IC8") (pin "44") (pinfunction "PA4/ADC4_44") (pintype "bidirectional"))
      (node (ref "TP4") (pin "TP") (pinfunction "TP_TP") (pintype "input"))
    )
    (net (code "40") (name "Net-(IC8-PA5{slash}ADC5)") (class "Default")
      (node (ref "IC8") (pin "1") (pinfunction "PA5/ADC5_1") (pintype "bidirectional"))
      (node (ref "TP5") (pin "TP") (pinfunction "TP_TP") (pintype "input"))
    )
    (net (code "41") (name "Net-(IC8-PB2{slash}ADC10{slash}DAC0)") (class "Default")
      (node (ref "IC8") (pin "6") (pinfunction "PB2/ADC10/DAC0_6") (pintype "bidirectional"))
      (node (ref "TP6") (pin "TP") (pinfunction "TP_TP") (pintype "input"))
    )
    (net (code "42") (name "Net-(IC8-PC1{slash}OC0B{slash}XCK0{slash}SCL)") (class "Default")
      (node (ref "IC8") (pin "11") (pinfunction "PC1/OC0B/XCK0/SCL_11") (pintype "bidirectional"))
      (node (ref "TP8") (pin "TP") (pinfunction "TP_TP") (pintype "input"))
    )
    (net (code "43") (name "Net-(IC8-PR1{slash}XTAL1)") (class "Default")
      (node (ref "IC8") (pin "37") (pinfunction "PR1/XTAL1_37") (pintype "bidirectional"))
      (node (ref "OSC1") (pin "P$3") (pinfunction "OUTPUT_P$3") (pintype "passive"))
    )
    (net (code "44") (name "Net-(IC9-OUT)") (class "Default")
      (node (ref "C24") (pin "1") (pinfunction "1_1") (pintype "passive"))
      (node (ref "IC9") (pin "5") (pinfunction "OUT_5") (pintype "bidirectional"))
      (node (ref "R5") (pin "1") (pinfunction "1_1") (pintype "passive"))
    )
    (net (code "45") (name "Net-(IC10-+IN)") (class "Default")
      (node (ref "IC10") (pin "3") (pinfunction "+IN_3") (pintype "input"))
      (node (ref "R20") (pin "1") (pinfunction "1_1") (pintype "passive"))
      (node (ref "R21") (pin "2") (pinfunction "2_2") (pintype "passive"))
    )
    (net (code "46") (name "Net-(IC10--IN)") (class "Default")
      (node (ref "IC10") (pin "1") (pinfunction "OUT_1") (pintype "output"))
      (node (ref "IC10") (pin "4") (pinfunction "-IN_4") (pintype "input"))
      (node (ref "R17") (pin "1") (pinfunction "1_1") (pintype "passive"))
    )
    (net (code "47") (name "Net-(R1-Pad2)") (class "Default")
      (node (ref "R1") (pin "2") (pinfunction "2_2") (pintype "passive"))
      (node (ref "STATE") (pin "C") (pinfunction "C_C") (pintype "passive"))
    )
    (net (code "48") (name "Net-(R2-Pad2)") (class "Default")
      (node (ref "R2") (pin "2") (pinfunction "2_2") (pintype "passive"))
      (node (ref "R5") (pin "2") (pinfunction "2_2") (pintype "passive"))
      (node (ref "X8") (pin "1") (pinfunction "1_1") (pintype "passive"))
    )
    (net (code "49") (name "Net-(X6-2)") (class "Default")
      (node (ref "IC7") (pin "P$4") (pinfunction "IO2_P$4") (pintype "bidirectional"))
      (node (ref "X6") (pin "P$2") (pinfunction "2_P$2") (pintype "bidirectional"))
    )
    (net (code "50") (name "Net-(X6-3)") (class "Default")
      (node (ref "IC7") (pin "P$6") (pinfunction "IO1_P$6") (pintype "bidirectional"))
      (node (ref "X6") (pin "P$3") (pinfunction "3_P$3") (pintype "bidirectional"))
    )
    (net (code "51") (name "Net-(X6-P$3)") (class "Default")
      (node (ref "C2") (pin "1") (pinfunction "1_1") (pintype "passive"))
      (node (ref "X6") (pin "SHIELD_3") (pinfunction "P$3_SHIELD_3") (pintype "bidirectional"))
    )
    (net (code "52") (name "Net-(X6-P$4)") (class "Default")
      (node (ref "R3") (pin "2") (pinfunction "2_2") (pintype "passive"))
      (node (ref "X6") (pin "SHIELD_4") (pinfunction "P$4_SHIELD_4") (pintype "bidirectional"))
    )
    (net (code "53") (name "VDD") (class "Default")
      (node (ref "X1") (pin "1") (pinfunction "1_1") (pintype "passive"))
      (node (ref "X7") (pin "P1") (pinfunction "1_P1") (pintype "passive"))
    )
    (net (code "54") (name "unconnected-(IC1-CBUS0-Pad23)") (class "Default")
      (node (ref "IC1") (pin "23") (pinfunction "CBUS0_23") (pintype "bidirectional"))
    )
    (net (code "55") (name "unconnected-(IC1-CBUS1-Pad22)") (class "Default")
      (node (ref "IC1") (pin "22") (pinfunction "CBUS1_22") (pintype "bidirectional"))
    )
    (net (code "56") (name "unconnected-(IC1-CBUS2-Pad13)") (class "Default")
      (node (ref "IC1") (pin "13") (pinfunction "CBUS2_13") (pintype "bidirectional"))
    )
    (net (code "57") (name "unconnected-(IC1-CBUS3-Pad14)") (class "Default")
      (node (ref "IC1") (pin "14") (pinfunction "CBUS3_14") (pintype "bidirectional"))
    )
    (net (code "58") (name "unconnected-(IC1-CBUS4-Pad12)") (class "Default")
      (node (ref "IC1") (pin "12") (pinfunction "CBUS4_12") (pintype "bidirectional"))
    )
    (net (code "59") (name "unconnected-(IC1-OSCI-Pad27)") (class "Default")
      (node (ref "IC1") (pin "27") (pinfunction "OSCI_27") (pintype "input"))
    )
    (net (code "60") (name "unconnected-(IC1-OSCO-Pad28)") (class "Default")
      (node (ref "IC1") (pin "28") (pinfunction "OSCO_28") (pintype "output"))
    )
    (net (code "61") (name "unconnected-(IC1-~{DCD}-Pad10)") (class "Default")
      (node (ref "IC1") (pin "10") (pinfunction "~{DCD}_10") (pintype "input"))
    )
    (net (code "62") (name "unconnected-(IC1-~{DSR}-Pad9)") (class "Default")
      (node (ref "IC1") (pin "9") (pinfunction "~{DSR}_9") (pintype "input"))
    )
    (net (code "63") (name "unconnected-(IC1-~{DTR}-Pad2)") (class "Default")
      (node (ref "IC1") (pin "2") (pinfunction "~{DTR}_2") (pintype "output"))
    )
    (net (code "64") (name "unconnected-(IC1-~{RI}-Pad6)") (class "Default")
      (node (ref "IC1") (pin "6") (pinfunction "~{RI}_6") (pintype "input"))
    )
    (net (code "65") (name "unconnected-(IC3-N{slash}C-Pad4)") (class "Default")
      (node (ref "IC3") (pin "4") (pinfunction "N/C_4") (pintype "bidirectional"))
    )
    (net (code "66") (name "unconnected-(IC8-D+{slash}TXD1{slash}SCK{slash}PD7-Pad27)") (class "Default")
      (node (ref "IC8") (pin "27") (pinfunction "D+/TXD1/SCK/PD7_27") (pintype "bidirectional"))
    )
    (net (code "67") (name "unconnected-(IC8-D-{slash}RXD1{slash}MISO{slash}PD6-Pad26)") (class "Default")
      (node (ref "IC8") (pin "26") (pinfunction "D-/RXD1/MISO/PD6_26") (pintype "bidirectional"))
    )
    (net (code "68") (name "unconnected-(IC8-OC0A{slash}PD0-Pad20)") (class "Default")
      (node (ref "IC8") (pin "20") (pinfunction "OC0A/PD0_20") (pintype "bidirectional"))
    )
    (net (code "69") (name "unconnected-(IC8-OC1A{slash}~{SS}{slash}PD4-Pad24)") (class "Default")
      (node (ref "IC8") (pin "24") (pinfunction "OC1A/~{SS}/PD4_24") (pintype "bidirectional"))
    )
    (net (code "70") (name "unconnected-(IC8-OCB1{slash}XCK1{slash}MOSI{slash}PD5-Pad25)") (class "Default")
      (node (ref "IC8") (pin "25") (pinfunction "OCB1/XCK1/MOSI/PD5_25") (pintype "bidirectional"))
    )
    (net (code "71") (name "unconnected-(IC8-PA3{slash}ADC3-Pad43)") (class "Default")
      (node (ref "IC8") (pin "43") (pinfunction "PA3/ADC3_43") (pintype "bidirectional"))
    )
    (net (code "72") (name "unconnected-(IC8-PA6{slash}ADC6{slash}AC1-OUT-Pad2)") (class "Default")
      (node (ref "IC8") (pin "2") (pinfunction "PA6/ADC6/AC1-OUT_2") (pintype "bidirectional"))
    )
    (net (code "73") (name "unconnected-(IC8-PA7{slash}ADC7{slash}AC0-OUT-Pad3)") (class "Default")
      (node (ref "IC8") (pin "3") (pinfunction "PA7/ADC7/AC0-OUT_3") (pintype "bidirectional"))
    )
    (net (code "74") (name "unconnected-(IC8-PB1{slash}ADC9-Pad5)") (class "Default")
      (node (ref "IC8") (pin "5") (pinfunction "PB1/ADC9_5") (pintype "bidirectional"))
    )
    (net (code "75") (name "unconnected-(IC8-PB3{slash}ADC11{slash}DAC1-Pad7)") (class "Default")
      (node (ref "IC8") (pin "7") (pinfunction "PB3/ADC11/DAC1_7") (pintype "bidirectional"))
    )
    (net (code "76") (name "unconnected-(IC8-PC7{slash}SCK{slash}TXD1{slash}CLKO{slash}EVO-Pad17)") (class "Default")
      (node (ref "IC8") (pin "17") (pinfunction "PC7/SCK/TXD1/CLKO/EVO_17") (pintype "bidirectional"))
    )
    (net (code "77") (name "unconnected-(IC9-N{slash}C-Pad4)") (class "Default")
      (node (ref "IC9") (pin "4") (pinfunction "N/C_4") (pintype "bidirectional"))
    )
    (net (code "78") (name "unconnected-(OSC1-STANDBY#-PadP$1)") (class "Default")
      (node (ref "OSC1") (pin "P$1") (pinfunction "STANDBY#_P$1") (pintype "passive"))
    )
    (net (code "79") (name "unconnected-(SV2-Pad3)") (class "Default")
      (node (ref "SV2") (pin "3") (pinfunction "3_3") (pintype "passive"))
    )
    (net (code "80") (name "unconnected-(SV2-Pad4)") (class "Default")
      (node (ref "SV2") (pin "4") (pinfunction "4_4") (pintype "passive"))
    )
    (net (code "81") (name "unconnected-(X2D-S-Pad4)") (class "Default")
      (node (ref "X2") (pin "4") (pinfunction "S_4") (pintype "passive"))
    )
    (net (code "82") (name "unconnected-(X6-4-PadP$4)") (class "Default")
      (node (ref "X6") (pin "P$4") (pinfunction "4_P$4") (pintype "bidirectional"))
    )
    (net (code "83") (name "unconnected-(X6-P$1-PadSHIELD_1)") (class "Default")
      (node (ref "X6") (pin "SHIELD_1") (pinfunction "P$1_SHIELD_1") (pintype "bidirectional"))
    )
    (net (code "84") (name "unconnected-(X6-P$2-PadSHIELD_2)") (class "Default")
      (node (ref "X6") (pin "SHIELD_2") (pinfunction "P$2_SHIELD_2") (pintype "bidirectional"))
    )
  )
)
